# PinBed.net
KiCad netlist of a schematic drawn in EAGLE
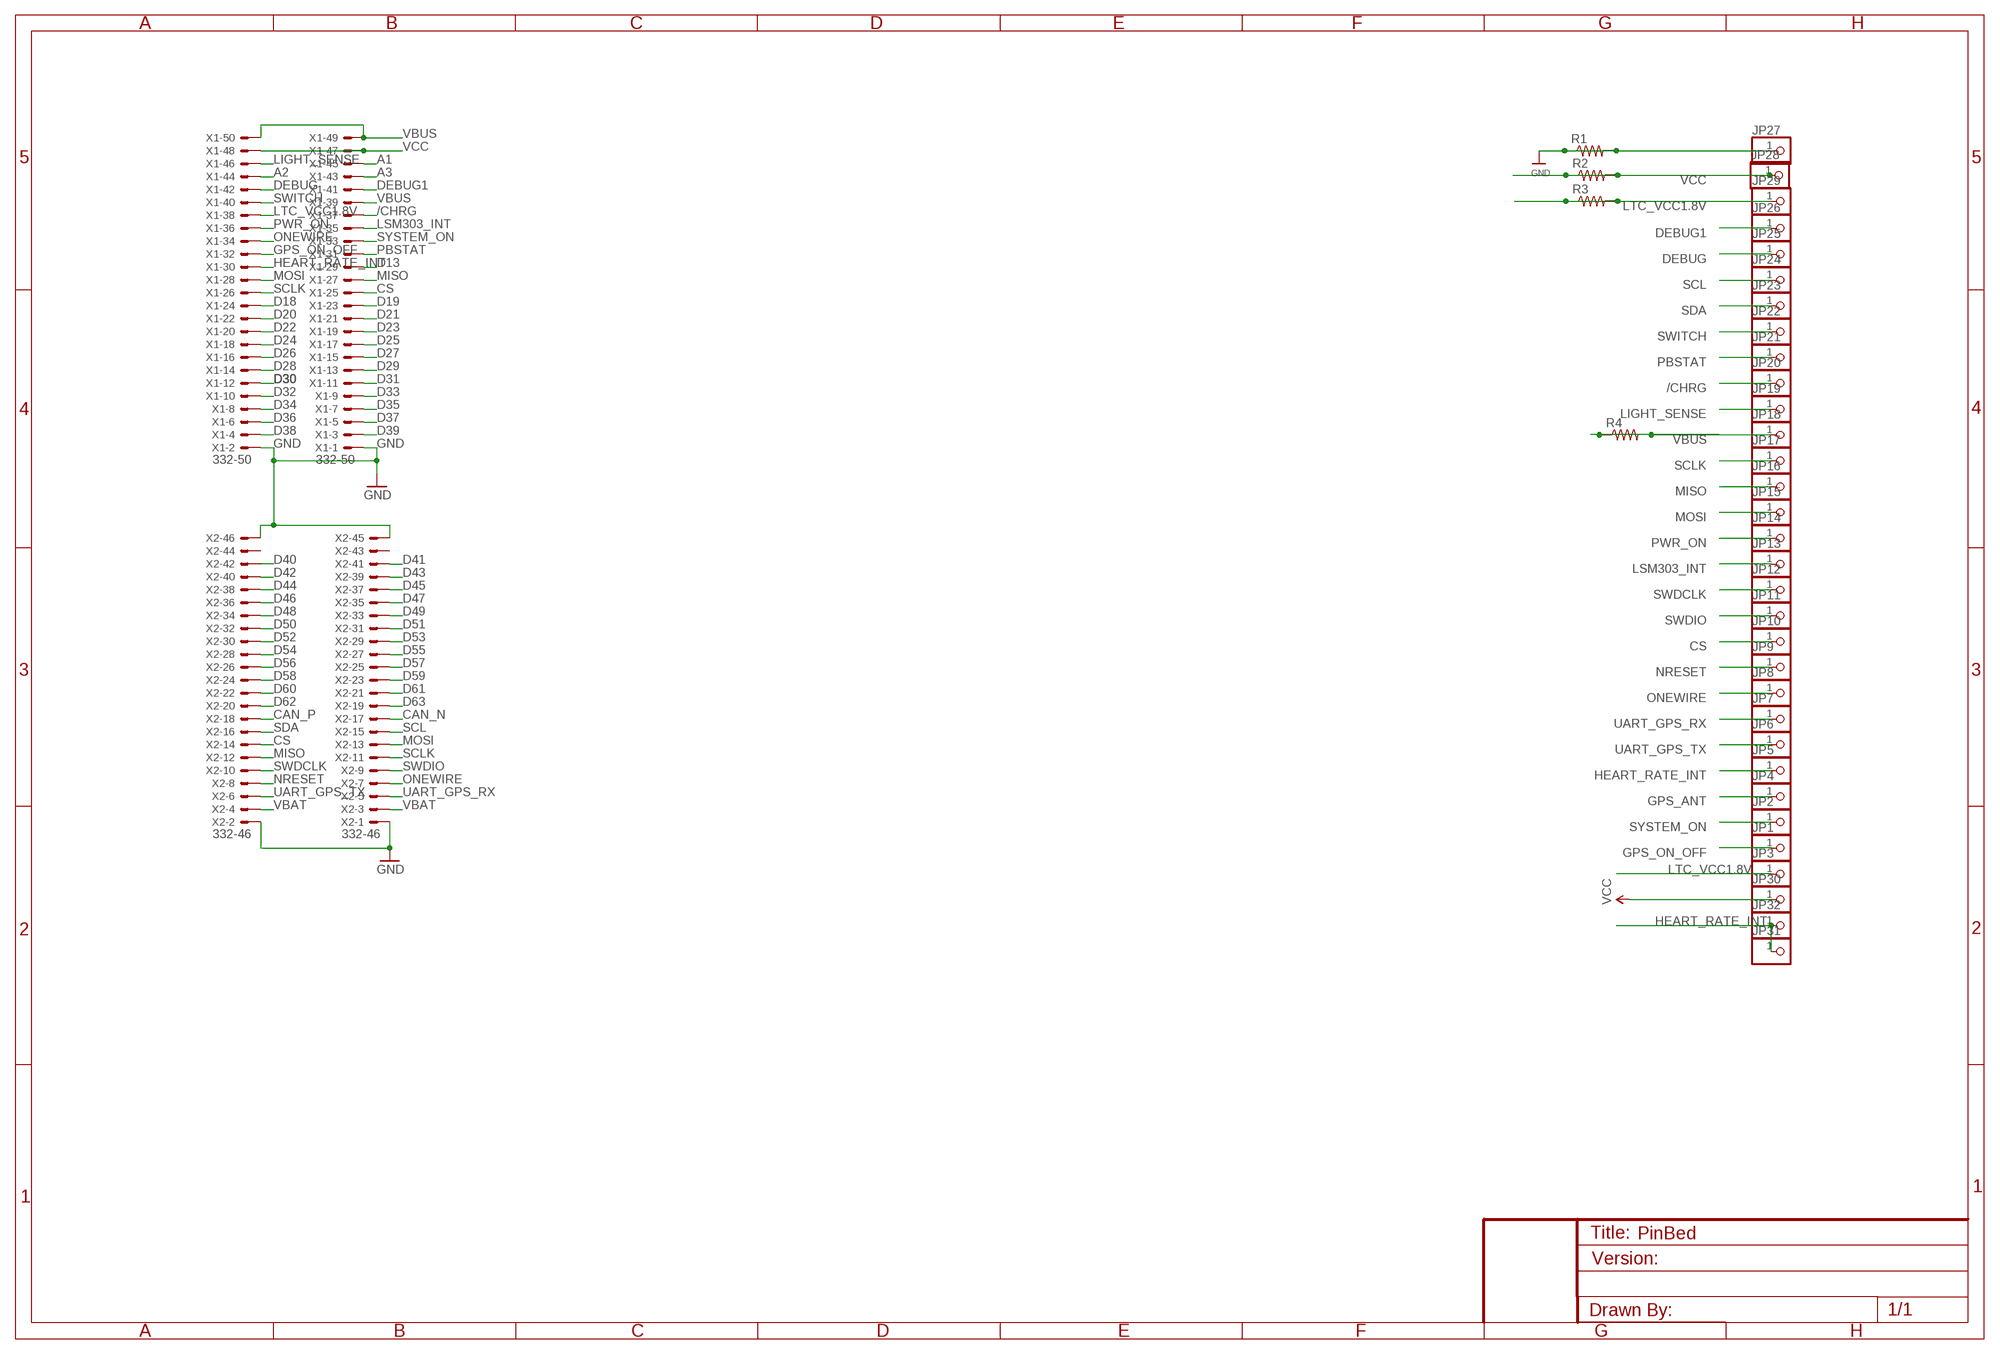
[diagram p0: schematic, sheet 1]

(export (version "E")
  (design (tool "Eeschema 10.0.6"))
  (components
    (comp (ref "JP1")
      (value "PINHD-1X1CB")
      (footprint "eagle-import:1X01-CLEANBIG")
      (libsource (lib "eagle-import") (part "PINHD-1X1CB"))
    )
    (comp (ref "JP2")
      (value "PINHD-1X1CB")
      (footprint "eagle-import:1X01-CLEANBIG")
      (libsource (lib "eagle-import") (part "PINHD-1X1CB"))
    )
    (comp (ref "JP3")
      (value "PINHD-1X1CB")
      (footprint "eagle-import:1X01-CLEANBIG")
      (libsource (lib "eagle-import") (part "PINHD-1X1CB"))
    )
    (comp (ref "JP4")
      (value "PINHD-1X1CB")
      (footprint "eagle-import:1X01-CLEANBIG")
      (libsource (lib "eagle-import") (part "PINHD-1X1CB"))
    )
    (comp (ref "JP5")
      (value "PINHD-1X1CB")
      (footprint "eagle-import:1X01-CLEANBIG")
      (libsource (lib "eagle-import") (part "PINHD-1X1CB"))
    )
    (comp (ref "JP6")
      (value "PINHD-1X1CB")
      (footprint "eagle-import:1X01-CLEANBIG")
      (libsource (lib "eagle-import") (part "PINHD-1X1CB"))
    )
    (comp (ref "JP7")
      (value "PINHD-1X1CB")
      (footprint "eagle-import:1X01-CLEANBIG")
      (libsource (lib "eagle-import") (part "PINHD-1X1CB"))
    )
    (comp (ref "JP8")
      (value "PINHD-1X1CB")
      (footprint "eagle-import:1X01-CLEANBIG")
      (libsource (lib "eagle-import") (part "PINHD-1X1CB"))
    )
    (comp (ref "JP9")
      (value "PINHD-1X1CB")
      (footprint "eagle-import:1X01-CLEANBIG")
      (libsource (lib "eagle-import") (part "PINHD-1X1CB"))
    )
    (comp (ref "JP10")
      (value "PINHD-1X1CB")
      (footprint "eagle-import:1X01-CLEANBIG")
      (libsource (lib "eagle-import") (part "PINHD-1X1CB"))
    )
    (comp (ref "JP11")
      (value "PINHD-1X1CB")
      (footprint "eagle-import:1X01-CLEANBIG")
      (libsource (lib "eagle-import") (part "PINHD-1X1CB"))
    )
    (comp (ref "JP12")
      (value "PINHD-1X1CB")
      (footprint "eagle-import:1X01-CLEANBIG")
      (libsource (lib "eagle-import") (part "PINHD-1X1CB"))
    )
    (comp (ref "JP13")
      (value "PINHD-1X1CB")
      (footprint "eagle-import:1X01-CLEANBIG")
      (libsource (lib "eagle-import") (part "PINHD-1X1CB"))
    )
    (comp (ref "JP14")
      (value "PINHD-1X1CB")
      (footprint "eagle-import:1X01-CLEANBIG")
      (libsource (lib "eagle-import") (part "PINHD-1X1CB"))
    )
    (comp (ref "JP15")
      (value "PINHD-1X1CB")
      (footprint "eagle-import:1X01-CLEANBIG")
      (libsource (lib "eagle-import") (part "PINHD-1X1CB"))
    )
    (comp (ref "JP16")
      (value "PINHD-1X1CB")
      (footprint "eagle-import:1X01-CLEANBIG")
      (libsource (lib "eagle-import") (part "PINHD-1X1CB"))
    )
    (comp (ref "JP17")
      (value "PINHD-1X1CB")
      (footprint "eagle-import:1X01-CLEANBIG")
      (libsource (lib "eagle-import") (part "PINHD-1X1CB"))
    )
    (comp (ref "JP18")
      (value "PINHD-1X1CB")
      (footprint "eagle-import:1X01-CLEANBIG")
      (libsource (lib "eagle-import") (part "PINHD-1X1CB"))
    )
    (comp (ref "JP19")
      (value "PINHD-1X1CB")
      (footprint "eagle-import:1X01-CLEANBIG")
      (libsource (lib "eagle-import") (part "PINHD-1X1CB"))
    )
    (comp (ref "JP20")
      (value "PINHD-1X1CB")
      (footprint "eagle-import:1X01-CLEANBIG")
      (libsource (lib "eagle-import") (part "PINHD-1X1CB"))
    )
    (comp (ref "JP21")
      (value "PINHD-1X1CB")
      (footprint "eagle-import:1X01-CLEANBIG")
      (libsource (lib "eagle-import") (part "PINHD-1X1CB"))
    )
    (comp (ref "JP22")
      (value "PINHD-1X1CB")
      (footprint "eagle-import:1X01-CLEANBIG")
      (libsource (lib "eagle-import") (part "PINHD-1X1CB"))
    )
    (comp (ref "JP23")
      (value "PINHD-1X1CB")
      (footprint "eagle-import:1X01-CLEANBIG")
      (libsource (lib "eagle-import") (part "PINHD-1X1CB"))
    )
    (comp (ref "JP24")
      (value "PINHD-1X1CB")
      (footprint "eagle-import:1X01-CLEANBIG")
      (libsource (lib "eagle-import") (part "PINHD-1X1CB"))
    )
    (comp (ref "JP25")
      (value "PINHD-1X1CB")
      (footprint "eagle-import:1X01-CLEANBIG")
      (libsource (lib "eagle-import") (part "PINHD-1X1CB"))
    )
    (comp (ref "JP26")
      (value "PINHD-1X1CB")
      (footprint "eagle-import:1X01-CLEANBIG")
      (libsource (lib "eagle-import") (part "PINHD-1X1CB"))
    )
    (comp (ref "JP27")
      (value "PINHD-1X1CB")
      (footprint "eagle-import:1X01-CLEANBIG")
      (libsource (lib "eagle-import") (part "PINHD-1X1CB"))
    )
    (comp (ref "JP28")
      (value "PINHD-1X1CB")
      (footprint "eagle-import:1X01-CLEANBIG")
      (libsource (lib "eagle-import") (part "PINHD-1X1CB"))
    )
    (comp (ref "JP29")
      (value "PINHD-1X1CB")
      (footprint "eagle-import:1X01-CLEANBIG")
      (libsource (lib "eagle-import") (part "PINHD-1X1CB"))
    )
    (comp (ref "JP30")
      (value "PINHD-1X1CB")
      (footprint "eagle-import:1X01-CLEANBIG")
      (libsource (lib "eagle-import") (part "PINHD-1X1CB"))
    )
    (comp (ref "JP31")
      (value "PINHD-1X1CB")
      (footprint "eagle-import:1X01-CLEANBIG")
      (libsource (lib "eagle-import") (part "PINHD-1X1CB"))
    )
    (comp (ref "JP32")
      (value "PINHD-1X1CB")
      (footprint "eagle-import:1X01-CLEANBIG")
      (libsource (lib "eagle-import") (part "PINHD-1X1CB"))
    )
    (comp (ref "R1")
      (value "RESISTOR0805-RES")
      (footprint "eagle-import:0805")
      (libsource (lib "eagle-import") (part "RESISTOR0805-RES"))
    )
    (comp (ref "R2")
      (value "RESISTOR0805-RES")
      (footprint "eagle-import:0805")
      (libsource (lib "eagle-import") (part "RESISTOR0805-RES"))
    )
    (comp (ref "R3")
      (value "RESISTOR0805-RES")
      (footprint "eagle-import:0805")
      (libsource (lib "eagle-import") (part "RESISTOR0805-RES"))
    )
    (comp (ref "R4")
      (value "RESISTOR0805-RES")
      (footprint "eagle-import:0805")
      (libsource (lib "eagle-import") (part "RESISTOR0805-RES"))
    )
    (comp (ref "X1")
      (value "332-50")
      (footprint "eagle-import:332-50")
      (libsource (lib "eagle-import") (part "332-50"))
    )
    (comp (ref "X2")
      (value "332-46")
      (footprint "eagle-import:332-46")
      (libsource (lib "eagle-import") (part "332-46"))
    )
  )
  (nets
    (net (code "1") (name "/A1") (class "Default")
      (node (ref "X1") (pin "45") (pinfunction "S_45") (pintype "passive"))
    )
    (net (code "2") (name "/A2") (class "Default")
      (node (ref "X1") (pin "44") (pinfunction "S_44") (pintype "passive"))
    )
    (net (code "3") (name "/A3") (class "Default")
      (node (ref "X1") (pin "43") (pinfunction "S_43") (pintype "passive"))
    )
    (net (code "4") (name "/CAN_N") (class "Default")
      (node (ref "X2") (pin "17") (pinfunction "S_17") (pintype "passive"))
    )
    (net (code "5") (name "/CAN_P") (class "Default")
      (node (ref "X2") (pin "18") (pinfunction "S_18") (pintype "passive"))
    )
    (net (code "6") (name "/CS") (class "Default")
      (node (ref "JP10") (pin "1") (pinfunction "1_1") (pintype "passive"))
      (node (ref "X1") (pin "25") (pinfunction "S_25") (pintype "passive"))
      (node (ref "X2") (pin "14") (pinfunction "S_14") (pintype "passive"))
    )
    (net (code "7") (name "/D13") (class "Default")
      (node (ref "X1") (pin "29") (pinfunction "S_29") (pintype "passive"))
    )
    (net (code "8") (name "/D18") (class "Default")
      (node (ref "X1") (pin "24") (pinfunction "S_24") (pintype "passive"))
    )
    (net (code "9") (name "/D19") (class "Default")
      (node (ref "X1") (pin "23") (pinfunction "S_23") (pintype "passive"))
    )
    (net (code "10") (name "/D20") (class "Default")
      (node (ref "X1") (pin "22") (pinfunction "S_22") (pintype "passive"))
    )
    (net (code "11") (name "/D21") (class "Default")
      (node (ref "X1") (pin "21") (pinfunction "S_21") (pintype "passive"))
    )
    (net (code "12") (name "/D22") (class "Default")
      (node (ref "X1") (pin "20") (pinfunction "S_20") (pintype "passive"))
    )
    (net (code "13") (name "/D23") (class "Default")
      (node (ref "X1") (pin "19") (pinfunction "S_19") (pintype "passive"))
    )
    (net (code "14") (name "/D24") (class "Default")
      (node (ref "X1") (pin "18") (pinfunction "S_18") (pintype "passive"))
    )
    (net (code "15") (name "/D25") (class "Default")
      (node (ref "X1") (pin "17") (pinfunction "S_17") (pintype "passive"))
    )
    (net (code "16") (name "/D26") (class "Default")
      (node (ref "X1") (pin "16") (pinfunction "S_16") (pintype "passive"))
    )
    (net (code "17") (name "/D27") (class "Default")
      (node (ref "X1") (pin "15") (pinfunction "S_15") (pintype "passive"))
    )
    (net (code "18") (name "/D28") (class "Default")
      (node (ref "X1") (pin "14") (pinfunction "S_14") (pintype "passive"))
    )
    (net (code "19") (name "/D29") (class "Default")
      (node (ref "X1") (pin "13") (pinfunction "S_13") (pintype "passive"))
    )
    (net (code "20") (name "/D30") (class "Default")
      (node (ref "X1") (pin "12") (pinfunction "S_12") (pintype "passive"))
    )
    (net (code "21") (name "/D31") (class "Default")
      (node (ref "X1") (pin "11") (pinfunction "S_11") (pintype "passive"))
    )
    (net (code "22") (name "/D32") (class "Default")
      (node (ref "X1") (pin "10") (pinfunction "S_10") (pintype "passive"))
    )
    (net (code "23") (name "/D33") (class "Default")
      (node (ref "X1") (pin "9") (pinfunction "S_9") (pintype "passive"))
    )
    (net (code "24") (name "/D34") (class "Default")
      (node (ref "X1") (pin "8") (pinfunction "S_8") (pintype "passive"))
    )
    (net (code "25") (name "/D35") (class "Default")
      (node (ref "X1") (pin "7") (pinfunction "S_7") (pintype "passive"))
    )
    (net (code "26") (name "/D36") (class "Default")
      (node (ref "X1") (pin "6") (pinfunction "S_6") (pintype "passive"))
    )
    (net (code "27") (name "/D37") (class "Default")
      (node (ref "X1") (pin "5") (pinfunction "S_5") (pintype "passive"))
    )
    (net (code "28") (name "/D38") (class "Default")
      (node (ref "X1") (pin "4") (pinfunction "S_4") (pintype "passive"))
    )
    (net (code "29") (name "/D39") (class "Default")
      (node (ref "X1") (pin "3") (pinfunction "S_3") (pintype "passive"))
    )
    (net (code "30") (name "/D40") (class "Default")
      (node (ref "X2") (pin "42") (pinfunction "S_42") (pintype "passive"))
    )
    (net (code "31") (name "/D41") (class "Default")
      (node (ref "X2") (pin "41") (pinfunction "S_41") (pintype "passive"))
    )
    (net (code "32") (name "/D42") (class "Default")
      (node (ref "X2") (pin "40") (pinfunction "S_40") (pintype "passive"))
    )
    (net (code "33") (name "/D43") (class "Default")
      (node (ref "X2") (pin "39") (pinfunction "S_39") (pintype "passive"))
    )
    (net (code "34") (name "/D44") (class "Default")
      (node (ref "X2") (pin "38") (pinfunction "S_38") (pintype "passive"))
    )
    (net (code "35") (name "/D45") (class "Default")
      (node (ref "X2") (pin "37") (pinfunction "S_37") (pintype "passive"))
    )
    (net (code "36") (name "/D46") (class "Default")
      (node (ref "X2") (pin "36") (pinfunction "S_36") (pintype "passive"))
    )
    (net (code "37") (name "/D47") (class "Default")
      (node (ref "X2") (pin "35") (pinfunction "S_35") (pintype "passive"))
    )
    (net (code "38") (name "/D48") (class "Default")
      (node (ref "X2") (pin "34") (pinfunction "S_34") (pintype "passive"))
    )
    (net (code "39") (name "/D49") (class "Default")
      (node (ref "X2") (pin "33") (pinfunction "S_33") (pintype "passive"))
    )
    (net (code "40") (name "/D50") (class "Default")
      (node (ref "X2") (pin "32") (pinfunction "S_32") (pintype "passive"))
    )
    (net (code "41") (name "/D51") (class "Default")
      (node (ref "X2") (pin "31") (pinfunction "S_31") (pintype "passive"))
    )
    (net (code "42") (name "/D52") (class "Default")
      (node (ref "X2") (pin "30") (pinfunction "S_30") (pintype "passive"))
    )
    (net (code "43") (name "/D53") (class "Default")
      (node (ref "X2") (pin "29") (pinfunction "S_29") (pintype "passive"))
    )
    (net (code "44") (name "/D54") (class "Default")
      (node (ref "X2") (pin "28") (pinfunction "S_28") (pintype "passive"))
    )
    (net (code "45") (name "/D55") (class "Default")
      (node (ref "X2") (pin "27") (pinfunction "S_27") (pintype "passive"))
    )
    (net (code "46") (name "/D56") (class "Default")
      (node (ref "X2") (pin "26") (pinfunction "S_26") (pintype "passive"))
    )
    (net (code "47") (name "/D57") (class "Default")
      (node (ref "X2") (pin "25") (pinfunction "S_25") (pintype "passive"))
    )
    (net (code "48") (name "/D58") (class "Default")
      (node (ref "X2") (pin "24") (pinfunction "S_24") (pintype "passive"))
    )
    (net (code "49") (name "/D59") (class "Default")
      (node (ref "X2") (pin "23") (pinfunction "S_23") (pintype "passive"))
    )
    (net (code "50") (name "/D60") (class "Default")
      (node (ref "X2") (pin "22") (pinfunction "S_22") (pintype "passive"))
    )
    (net (code "51") (name "/D61") (class "Default")
      (node (ref "X2") (pin "21") (pinfunction "S_21") (pintype "passive"))
    )
    (net (code "52") (name "/D62") (class "Default")
      (node (ref "X2") (pin "20") (pinfunction "S_20") (pintype "passive"))
    )
    (net (code "53") (name "/D63") (class "Default")
      (node (ref "X2") (pin "19") (pinfunction "S_19") (pintype "passive"))
    )
    (net (code "54") (name "/DEBUG") (class "Default")
      (node (ref "JP25") (pin "1") (pinfunction "1_1") (pintype "passive"))
      (node (ref "X1") (pin "42") (pinfunction "S_42") (pintype "passive"))
    )
    (net (code "55") (name "/DEBUG1") (class "Default")
      (node (ref "JP26") (pin "1") (pinfunction "1_1") (pintype "passive"))
      (node (ref "X1") (pin "41") (pinfunction "S_41") (pintype "passive"))
    )
    (net (code "56") (name "/GPS_ANT") (class "Default")
      (node (ref "JP4") (pin "1") (pinfunction "1_1") (pintype "passive"))
    )
    (net (code "57") (name "/GPS_ON_OFF") (class "Default")
      (node (ref "JP1") (pin "1") (pinfunction "1_1") (pintype "passive"))
      (node (ref "X1") (pin "32") (pinfunction "S_32") (pintype "passive"))
    )
    (net (code "58") (name "/HEART_RATE_INT") (class "Default")
      (node (ref "JP31") (pin "1") (pinfunction "1_1") (pintype "passive"))
      (node (ref "JP32") (pin "1") (pinfunction "1_1") (pintype "passive"))
      (node (ref "JP5") (pin "1") (pinfunction "1_1") (pintype "passive"))
      (node (ref "X1") (pin "30") (pinfunction "S_30") (pintype "passive"))
    )
    (net (code "59") (name "/LIGHT_SENSE") (class "Default")
      (node (ref "JP19") (pin "1") (pinfunction "1_1") (pintype "passive"))
      (node (ref "X1") (pin "46") (pinfunction "S_46") (pintype "passive"))
    )
    (net (code "60") (name "/LSM303_INT") (class "Default")
      (node (ref "JP13") (pin "1") (pinfunction "1_1") (pintype "passive"))
      (node (ref "X1") (pin "35") (pinfunction "S_35") (pintype "passive"))
    )
    (net (code "61") (name "/LTC_VCC1.8V") (class "Default")
      (node (ref "JP29") (pin "1") (pinfunction "1_1") (pintype "passive"))
      (node (ref "JP3") (pin "1") (pinfunction "1_1") (pintype "passive"))
      (node (ref "R3") (pin "1") (pinfunction "1_1") (pintype "passive"))
      (node (ref "R3") (pin "2") (pinfunction "2_2") (pintype "passive"))
      (node (ref "X1") (pin "38") (pinfunction "S_38") (pintype "passive"))
    )
    (net (code "62") (name "/MISO") (class "Default")
      (node (ref "JP16") (pin "1") (pinfunction "1_1") (pintype "passive"))
      (node (ref "X1") (pin "27") (pinfunction "S_27") (pintype "passive"))
      (node (ref "X2") (pin "12") (pinfunction "S_12") (pintype "passive"))
    )
    (net (code "63") (name "/MOSI") (class "Default")
      (node (ref "JP15") (pin "1") (pinfunction "1_1") (pintype "passive"))
      (node (ref "X1") (pin "28") (pinfunction "S_28") (pintype "passive"))
      (node (ref "X2") (pin "13") (pinfunction "S_13") (pintype "passive"))
    )
    (net (code "64") (name "/NRESET") (class "Default")
      (node (ref "JP9") (pin "1") (pinfunction "1_1") (pintype "passive"))
      (node (ref "X2") (pin "8") (pinfunction "S_8") (pintype "passive"))
    )
    (net (code "65") (name "/ONEWIRE") (class "Default")
      (node (ref "JP8") (pin "1") (pinfunction "1_1") (pintype "passive"))
      (node (ref "X1") (pin "34") (pinfunction "S_34") (pintype "passive"))
      (node (ref "X2") (pin "7") (pinfunction "S_7") (pintype "passive"))
    )
    (net (code "66") (name "/PBSTAT") (class "Default")
      (node (ref "JP21") (pin "1") (pinfunction "1_1") (pintype "passive"))
      (node (ref "X1") (pin "31") (pinfunction "S_31") (pintype "passive"))
    )
    (net (code "67") (name "/PWR_ON") (class "Default")
      (node (ref "JP14") (pin "1") (pinfunction "1_1") (pintype "passive"))
      (node (ref "X1") (pin "36") (pinfunction "S_36") (pintype "passive"))
    )
    (net (code "68") (name "/SCL") (class "Default")
      (node (ref "JP24") (pin "1") (pinfunction "1_1") (pintype "passive"))
      (node (ref "X2") (pin "15") (pinfunction "S_15") (pintype "passive"))
    )
    (net (code "69") (name "/SCLK") (class "Default")
      (node (ref "JP17") (pin "1") (pinfunction "1_1") (pintype "passive"))
      (node (ref "X1") (pin "26") (pinfunction "S_26") (pintype "passive"))
      (node (ref "X2") (pin "11") (pinfunction "S_11") (pintype "passive"))
    )
    (net (code "70") (name "/SDA") (class "Default")
      (node (ref "JP23") (pin "1") (pinfunction "1_1") (pintype "passive"))
      (node (ref "X2") (pin "16") (pinfunction "S_16") (pintype "passive"))
    )
    (net (code "71") (name "/SWDCLK") (class "Default")
      (node (ref "JP12") (pin "1") (pinfunction "1_1") (pintype "passive"))
      (node (ref "X2") (pin "10") (pinfunction "S_10") (pintype "passive"))
    )
    (net (code "72") (name "/SWDIO") (class "Default")
      (node (ref "JP11") (pin "1") (pinfunction "1_1") (pintype "passive"))
      (node (ref "X2") (pin "9") (pinfunction "S_9") (pintype "passive"))
    )
    (net (code "73") (name "/SWITCH") (class "Default")
      (node (ref "JP22") (pin "1") (pinfunction "1_1") (pintype "passive"))
      (node (ref "X1") (pin "40") (pinfunction "S_40") (pintype "passive"))
    )
    (net (code "74") (name "/SYSTEM_ON") (class "Default")
      (node (ref "JP2") (pin "1") (pinfunction "1_1") (pintype "passive"))
      (node (ref "X1") (pin "33") (pinfunction "S_33") (pintype "passive"))
    )
    (net (code "75") (name "/UART_GPS_RX") (class "Default")
      (node (ref "JP7") (pin "1") (pinfunction "1_1") (pintype "passive"))
      (node (ref "X2") (pin "5") (pinfunction "S_5") (pintype "passive"))
    )
    (net (code "76") (name "/UART_GPS_TX") (class "Default")
      (node (ref "JP6") (pin "1") (pinfunction "1_1") (pintype "passive"))
      (node (ref "X2") (pin "6") (pinfunction "S_6") (pintype "passive"))
    )
    (net (code "77") (name "/VBAT") (class "Default")
      (node (ref "X2") (pin "3") (pinfunction "S_3") (pintype "passive"))
      (node (ref "X2") (pin "4") (pinfunction "S_4") (pintype "passive"))
    )
    (net (code "78") (name "/VBUS") (class "Default")
      (node (ref "JP18") (pin "1") (pinfunction "1_1") (pintype "passive"))
      (node (ref "R4") (pin "1") (pinfunction "1_1") (pintype "passive"))
      (node (ref "R4") (pin "2") (pinfunction "2_2") (pintype "passive"))
      (node (ref "X1") (pin "39") (pinfunction "S_39") (pintype "passive"))
      (node (ref "X1") (pin "49") (pinfunction "S_49") (pintype "passive"))
      (node (ref "X1") (pin "50") (pinfunction "S_50") (pintype "passive"))
    )
    (net (code "79") (name "/{slash}CHRG") (class "Default")
      (node (ref "JP20") (pin "1") (pinfunction "1_1") (pintype "passive"))
      (node (ref "X1") (pin "37") (pinfunction "S_37") (pintype "passive"))
    )
    (net (code "80") (name "GND") (class "Default")
      (node (ref "JP27") (pin "1") (pinfunction "1_1") (pintype "passive"))
      (node (ref "R1") (pin "1") (pinfunction "1_1") (pintype "passive"))
      (node (ref "R1") (pin "2") (pinfunction "2_2") (pintype "passive"))
      (node (ref "X1") (pin "1") (pinfunction "S_1") (pintype "passive"))
      (node (ref "X1") (pin "2") (pinfunction "S_2") (pintype "passive"))
      (node (ref "X2") (pin "1") (pinfunction "S_1") (pintype "passive"))
      (node (ref "X2") (pin "2") (pinfunction "S_2") (pintype "passive"))
      (node (ref "X2") (pin "45") (pinfunction "S_45") (pintype "passive"))
      (node (ref "X2") (pin "46") (pinfunction "S_46") (pintype "passive"))
    )
    (net (code "81") (name "VCC") (class "Default")
      (node (ref "JP28") (pin "1") (pinfunction "1_1") (pintype "passive"))
      (node (ref "JP30") (pin "1") (pinfunction "1_1") (pintype "passive"))
      (node (ref "R2") (pin "1") (pinfunction "1_1") (pintype "passive"))
      (node (ref "R2") (pin "2") (pinfunction "2_2") (pintype "passive"))
      (node (ref "X1") (pin "47") (pinfunction "S_47") (pintype "passive"))
      (node (ref "X1") (pin "48") (pinfunction "S_48") (pintype "passive"))
    )
    (net (code "82") (name "unconnected-(X2AL-S-Pad43)") (class "Default")
      (node (ref "X2") (pin "43") (pinfunction "S_43") (pintype "passive"))
    )
    (net (code "83") (name "unconnected-(X2AM-S-Pad44)") (class "Default")
      (node (ref "X2") (pin "44") (pinfunction "S_44") (pintype "passive"))
    )
  )
)
